# atmegademo.net
KiCad netlist of a schematic drawn in EAGLE
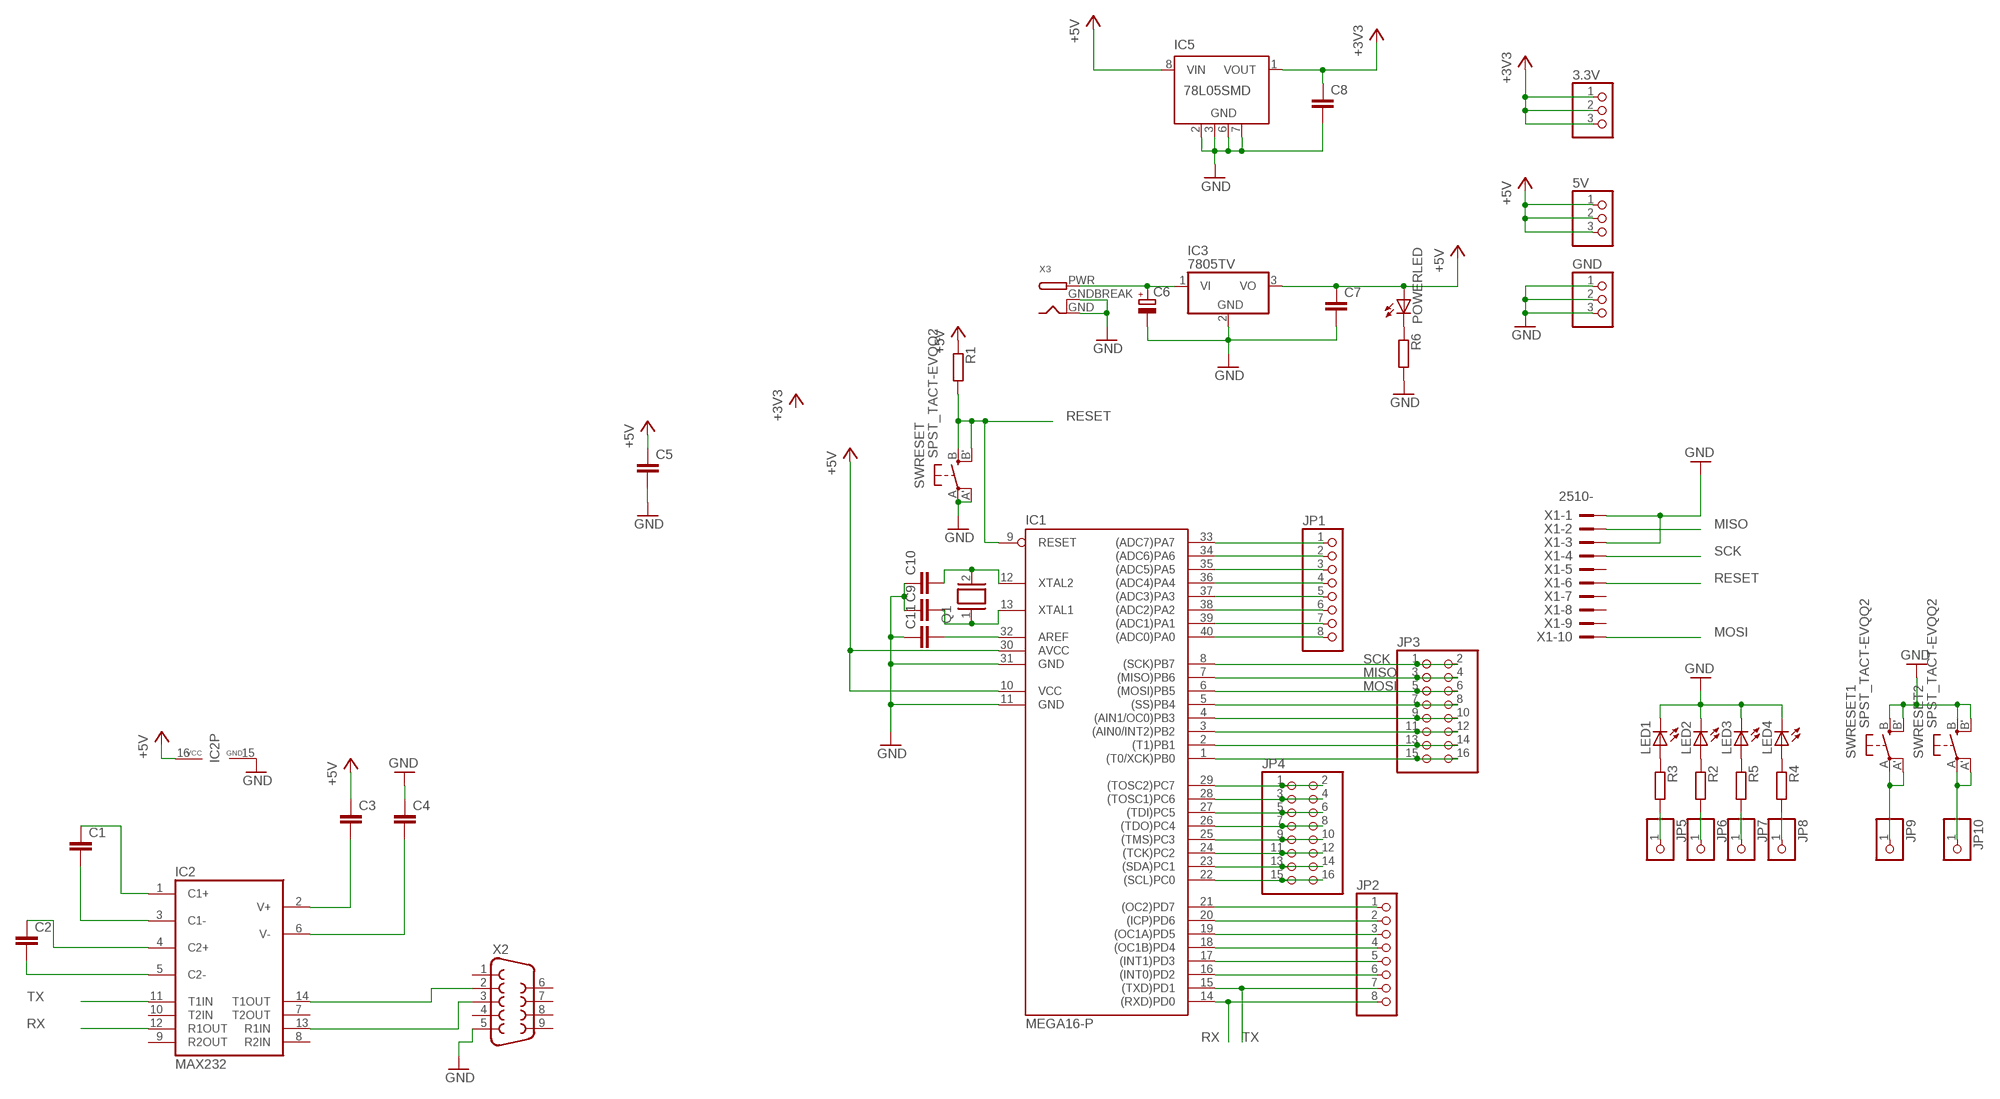
[diagram p0: schematic, sheet 1]

(export (version "E")
  (design (tool "Eeschema 10.0.6"))
  (components
    (comp (ref "3.3V")
      (value "PINHD-1X3")
      (footprint "eagle-import:1X03")
      (libsource (lib "eagle-import") (part "PINHD-1X3"))
    )
    (comp (ref "5V")
      (value "PINHD-1X3")
      (footprint "eagle-import:1X03")
      (libsource (lib "eagle-import") (part "PINHD-1X3"))
    )
    (comp (ref "C1")
      (value "C-EUC0805K")
      (footprint "eagle-import:C0805K")
      (libsource (lib "eagle-import") (part "C-EUC0805K"))
    )
    (comp (ref "C2")
      (value "C-EUC0805K")
      (footprint "eagle-import:C0805K")
      (libsource (lib "eagle-import") (part "C-EUC0805K"))
    )
    (comp (ref "C3")
      (value "C-EUC0805K")
      (footprint "eagle-import:C0805K")
      (libsource (lib "eagle-import") (part "C-EUC0805K"))
    )
    (comp (ref "C4")
      (value "C-EUC0805K")
      (footprint "eagle-import:C0805K")
      (libsource (lib "eagle-import") (part "C-EUC0805K"))
    )
    (comp (ref "C5")
      (value "C-EUC0805K")
      (footprint "eagle-import:C0805K")
      (libsource (lib "eagle-import") (part "C-EUC0805K"))
    )
    (comp (ref "C6")
      (value "CPOL-EUE2.5-5")
      (footprint "eagle-import:E2,5-5")
      (libsource (lib "eagle-import") (part "CPOL-EUE2.5-5"))
    )
    (comp (ref "C7")
      (value "C-EUC0805K")
      (footprint "eagle-import:C0805K")
      (libsource (lib "eagle-import") (part "C-EUC0805K"))
    )
    (comp (ref "C8")
      (value "C-EUC0805K")
      (footprint "eagle-import:C0805K")
      (libsource (lib "eagle-import") (part "C-EUC0805K"))
    )
    (comp (ref "C9")
      (value "C-EU050-025X075")
      (footprint "eagle-import:C050-025X075")
      (libsource (lib "eagle-import") (part "C-EU050-025X075"))
    )
    (comp (ref "C10")
      (value "C-EU050-025X075")
      (footprint "eagle-import:C050-025X075")
      (libsource (lib "eagle-import") (part "C-EU050-025X075"))
    )
    (comp (ref "C11")
      (value "C-EUC0805K")
      (footprint "eagle-import:C0805K")
      (libsource (lib "eagle-import") (part "C-EUC0805K"))
    )
    (comp (ref "GND")
      (value "PINHD-1X3")
      (footprint "eagle-import:1X03")
      (libsource (lib "eagle-import") (part "PINHD-1X3"))
    )
    (comp (ref "IC1")
      (value "MEGA16-P")
      (footprint "eagle-import:DIL40")
      (fields (field (name "MPN") "ATMEGA16-16PU"))
      (libsource (lib "eagle-import") (part "MEGA16-P"))
    )
    (comp (ref "IC2")
      (value "MAX232")
      (footprint "eagle-import:DIL16")
      (fields (field (name "MF") "MAXIM") (field (name "MPN") "MAX232ACPE+"))
      (libsource (lib "eagle-import") (part "MAX232"))
    )
    (comp (ref "IC3")
      (value "7805TV")
      (footprint "eagle-import:TO220V")
      (libsource (lib "eagle-import") (part "78TV05"))
    )
    (comp (ref "IC5")
      (value "78L05SMD")
      (footprint "eagle-import:SO08")
      (libsource (lib "eagle-import") (part "78LSMD05"))
    )
    (comp (ref "JP1")
      (value "PINHD-1X8BIG")
      (footprint "eagle-import:1X08-BIG")
      (libsource (lib "eagle-import") (part "PINHD-1X8BIG"))
    )
    (comp (ref "JP2")
      (value "PINHD-1X8BIG")
      (footprint "eagle-import:1X08-BIG")
      (libsource (lib "eagle-import") (part "PINHD-1X8BIG"))
    )
    (comp (ref "JP3")
      (value "PINHD-2X8")
      (footprint "eagle-import:2X08")
      (libsource (lib "eagle-import") (part "PINHD-2X8"))
    )
    (comp (ref "JP4")
      (value "PINHD-2X8")
      (footprint "eagle-import:2X08")
      (libsource (lib "eagle-import") (part "PINHD-2X8"))
    )
    (comp (ref "JP5")
      (value "PINHD-1X1")
      (footprint "eagle-import:1X01")
      (libsource (lib "eagle-import") (part "PINHD-1X1"))
    )
    (comp (ref "JP6")
      (value "PINHD-1X1")
      (footprint "eagle-import:1X01")
      (libsource (lib "eagle-import") (part "PINHD-1X1"))
    )
    (comp (ref "JP7")
      (value "PINHD-1X1")
      (footprint "eagle-import:1X01")
      (libsource (lib "eagle-import") (part "PINHD-1X1"))
    )
    (comp (ref "JP8")
      (value "PINHD-1X1")
      (footprint "eagle-import:1X01")
      (libsource (lib "eagle-import") (part "PINHD-1X1"))
    )
    (comp (ref "JP9")
      (value "PINHD-1X1")
      (footprint "eagle-import:1X01")
      (libsource (lib "eagle-import") (part "PINHD-1X1"))
    )
    (comp (ref "JP10")
      (value "PINHD-1X1")
      (footprint "eagle-import:1X01")
      (libsource (lib "eagle-import") (part "PINHD-1X1"))
    )
    (comp (ref "LED1")
      (value "LED3MM")
      (footprint "eagle-import:LED3MM")
      (libsource (lib "eagle-import") (part "LED3MM"))
    )
    (comp (ref "LED2")
      (value "LED3MM")
      (footprint "eagle-import:LED3MM")
      (libsource (lib "eagle-import") (part "LED3MM"))
    )
    (comp (ref "LED3")
      (value "LED3MM")
      (footprint "eagle-import:LED3MM")
      (libsource (lib "eagle-import") (part "LED3MM"))
    )
    (comp (ref "LED4")
      (value "LED3MM")
      (footprint "eagle-import:LED3MM")
      (libsource (lib "eagle-import") (part "LED3MM"))
    )
    (comp (ref "POWERLED")
      (value "LED3MM")
      (footprint "eagle-import:LED3MM")
      (libsource (lib "eagle-import") (part "LED3MM"))
    )
    (comp (ref "Q1")
      (value "XTAL/S")
      (footprint "eagle-import:QS")
      (libsource (lib "eagle-import") (part "XTAL/S"))
    )
    (comp (ref "R1")
      (value "R-EU_0207/12")
      (footprint "eagle-import:0207_12")
      (libsource (lib "eagle-import") (part "R-EU_0207/12"))
    )
    (comp (ref "R2")
      (value "R-EU_R0805")
      (footprint "eagle-import:R0805")
      (libsource (lib "eagle-import") (part "R-EU_R0805"))
    )
    (comp (ref "R3")
      (value "R-EU_M0805")
      (footprint "eagle-import:M0805")
      (libsource (lib "eagle-import") (part "R-EU_M0805"))
    )
    (comp (ref "R4")
      (value "R-EU_R0805")
      (footprint "eagle-import:R0805")
      (libsource (lib "eagle-import") (part "R-EU_R0805"))
    )
    (comp (ref "R5")
      (value "R-EU_M0805")
      (footprint "eagle-import:M0805")
      (libsource (lib "eagle-import") (part "R-EU_M0805"))
    )
    (comp (ref "R6")
      (value "R-EU_M0805")
      (footprint "eagle-import:M0805")
      (libsource (lib "eagle-import") (part "R-EU_M0805"))
    )
    (comp (ref "SWRESET")
      (value "SPST_TACT-EVQQ2")
      (footprint "eagle-import:EVQ-Q2")
      (libsource (lib "eagle-import") (part "SPST_TACT-EVQQ2"))
    )
    (comp (ref "SWRESET1")
      (value "SPST_TACT-EVQQ2")
      (footprint "eagle-import:EVQ-Q2")
      (libsource (lib "eagle-import") (part "SPST_TACT-EVQQ2"))
    )
    (comp (ref "SWRESET2")
      (value "SPST_TACT-EVQQ2")
      (footprint "eagle-import:EVQ-Q2")
      (libsource (lib "eagle-import") (part "SPST_TACT-EVQQ2"))
    )
    (comp (ref "X1")
      (value "2510-")
      (footprint "eagle-import:PAK100_2500-10")
      (fields (field (name "MF") "3M") (field (name "MPN") "2510-6002UB"))
      (libsource (lib "eagle-import") (part "2510-"))
    )
    (comp (ref "X2")
      (value "F09H")
      (footprint "eagle-import:F09H")
      (libsource (lib "eagle-import") (part "F09H"))
    )
    (comp (ref "X3")
      (value "DCBARRELPTH")
      (footprint "eagle-import:DCJACK_2MM_PTH")
      (libsource (lib "eagle-import") (part "DCBARRELPTH"))
    )
  )
  (nets
    (net (code "1") (name "+3V3") (class "Default")
      (node (ref "3.3V") (pin "1") (pinfunction "1_1") (pintype "passive"))
      (node (ref "3.3V") (pin "2") (pinfunction "2_2") (pintype "passive"))
      (node (ref "3.3V") (pin "3") (pinfunction "3_3") (pintype "passive"))
      (node (ref "C8") (pin "1") (pinfunction "1_1") (pintype "passive"))
      (node (ref "IC5") (pin "1") (pinfunction "VOUT_1") (pintype "output"))
    )
    (net (code "2") (name "+5V") (class "Default")
      (node (ref "5V") (pin "1") (pinfunction "1_1") (pintype "passive"))
      (node (ref "5V") (pin "2") (pinfunction "2_2") (pintype "passive"))
      (node (ref "5V") (pin "3") (pinfunction "3_3") (pintype "passive"))
      (node (ref "C3") (pin "1") (pinfunction "1_1") (pintype "passive"))
      (node (ref "C5") (pin "1") (pinfunction "1_1") (pintype "passive"))
      (node (ref "C7") (pin "1") (pinfunction "1_1") (pintype "passive"))
      (node (ref "IC1") (pin "10") (pinfunction "VCC_10") (pintype "power_in"))
      (node (ref "IC1") (pin "30") (pinfunction "AVCC_30") (pintype "power_in"))
      (node (ref "IC2") (pin "16") (pinfunction "VCC_16") (pintype "power_in"))
      (node (ref "IC3") (pin "3") (pinfunction "VO_3") (pintype "passive"))
      (node (ref "IC5") (pin "8") (pinfunction "VIN_8") (pintype "passive"))
      (node (ref "POWERLED") (pin "A") (pinfunction "A_A") (pintype "passive"))
      (node (ref "R1") (pin "1") (pinfunction "1_1") (pintype "passive"))
    )
    (net (code "3") (name "/MISO") (class "Default")
      (node (ref "IC1") (pin "7") (pinfunction "(MISO)PB6_7") (pintype "bidirectional"))
      (node (ref "JP3") (pin "3") (pinfunction "3_3") (pintype "passive"))
      (node (ref "JP3") (pin "4") (pinfunction "4_4") (pintype "passive"))
      (node (ref "X1") (pin "2") (pinfunction "KL_2") (pintype "passive"))
    )
    (net (code "4") (name "/MOSI") (class "Default")
      (node (ref "IC1") (pin "6") (pinfunction "(MOSI)PB5_6") (pintype "bidirectional"))
      (node (ref "JP3") (pin "5") (pinfunction "5_5") (pintype "passive"))
      (node (ref "JP3") (pin "6") (pinfunction "6_6") (pintype "passive"))
      (node (ref "X1") (pin "10") (pinfunction "KL_10") (pintype "passive"))
    )
    (net (code "5") (name "/RESET") (class "Default")
      (node (ref "IC1") (pin "9") (pinfunction "RESET_9") (pintype "input"))
      (node (ref "R1") (pin "2") (pinfunction "2_2") (pintype "passive"))
      (node (ref "SWRESET") (pin "B") (pinfunction "S_B") (pintype "passive"))
      (node (ref "SWRESET") (pin "B'") (pinfunction "S1_B'") (pintype "passive"))
      (node (ref "X1") (pin "6") (pinfunction "KL_6") (pintype "passive"))
    )
    (net (code "6") (name "/RX") (class "Default")
      (node (ref "IC1") (pin "14") (pinfunction "(RXD)PD0_14") (pintype "bidirectional"))
      (node (ref "IC2") (pin "12") (pinfunction "R1OUT_12") (pintype "output"))
      (node (ref "JP2") (pin "8") (pinfunction "8_8") (pintype "passive"))
    )
    (net (code "7") (name "/SCK") (class "Default")
      (node (ref "IC1") (pin "8") (pinfunction "(SCK)PB7_8") (pintype "bidirectional"))
      (node (ref "JP3") (pin "1") (pinfunction "1_1") (pintype "passive"))
      (node (ref "JP3") (pin "2") (pinfunction "2_2") (pintype "passive"))
      (node (ref "X1") (pin "4") (pinfunction "KL_4") (pintype "passive"))
    )
    (net (code "8") (name "/TX") (class "Default")
      (node (ref "IC1") (pin "15") (pinfunction "(TXD)PD1_15") (pintype "bidirectional"))
      (node (ref "IC2") (pin "11") (pinfunction "T1IN_11") (pintype "input"))
      (node (ref "JP2") (pin "7") (pinfunction "7_7") (pintype "passive"))
    )
    (net (code "9") (name "GND") (class "Default")
      (node (ref "C10") (pin "1") (pinfunction "1_1") (pintype "passive"))
      (node (ref "C11") (pin "1") (pinfunction "1_1") (pintype "passive"))
      (node (ref "C4") (pin "1") (pinfunction "1_1") (pintype "passive"))
      (node (ref "C5") (pin "2") (pinfunction "2_2") (pintype "passive"))
      (node (ref "C6") (pin "-") (pinfunction "-_-") (pintype "passive"))
      (node (ref "C7") (pin "2") (pinfunction "2_2") (pintype "passive"))
      (node (ref "C8") (pin "2") (pinfunction "2_2") (pintype "passive"))
      (node (ref "C9") (pin "1") (pinfunction "1_1") (pintype "passive"))
      (node (ref "GND") (pin "1") (pinfunction "1_1") (pintype "passive"))
      (node (ref "GND") (pin "2") (pinfunction "2_2") (pintype "passive"))
      (node (ref "GND") (pin "3") (pinfunction "3_3") (pintype "passive"))
      (node (ref "IC1") (pin "11") (pinfunction "GND_11") (pintype "power_in"))
      (node (ref "IC1") (pin "31") (pinfunction "GND_31") (pintype "power_in"))
      (node (ref "IC2") (pin "15") (pinfunction "GND_15") (pintype "power_in"))
      (node (ref "IC3") (pin "2") (pinfunction "GND_2") (pintype "passive"))
      (node (ref "IC5") (pin "2") (pinfunction "GND_2") (pintype "power_in"))
      (node (ref "IC5") (pin "3") (pinfunction "GND_3") (pintype "power_in"))
      (node (ref "IC5") (pin "6") (pinfunction "GND_6") (pintype "power_in"))
      (node (ref "IC5") (pin "7") (pinfunction "GND_7") (pintype "power_in"))
      (node (ref "LED1") (pin "K") (pinfunction "C_K") (pintype "passive"))
      (node (ref "LED2") (pin "K") (pinfunction "C_K") (pintype "passive"))
      (node (ref "LED3") (pin "K") (pinfunction "C_K") (pintype "passive"))
      (node (ref "LED4") (pin "K") (pinfunction "C_K") (pintype "passive"))
      (node (ref "R6") (pin "2") (pinfunction "2_2") (pintype "passive"))
      (node (ref "SWRESET") (pin "A") (pinfunction "P_A") (pintype "passive"))
      (node (ref "SWRESET") (pin "A'") (pinfunction "P1_A'") (pintype "passive"))
      (node (ref "SWRESET1") (pin "B") (pinfunction "S_B") (pintype "passive"))
      (node (ref "SWRESET1") (pin "B'") (pinfunction "S1_B'") (pintype "passive"))
      (node (ref "SWRESET2") (pin "B") (pinfunction "S_B") (pintype "passive"))
      (node (ref "SWRESET2") (pin "B'") (pinfunction "S1_B'") (pintype "passive"))
      (node (ref "X1") (pin "1") (pinfunction "KL_1") (pintype "passive"))
      (node (ref "X1") (pin "3") (pinfunction "KL_3") (pintype "passive"))
      (node (ref "X2") (pin "5") (pinfunction "5_5") (pintype "passive"))
      (node (ref "X3") (pin "GND") (pinfunction "GND_GND") (pintype "power_in"))
      (node (ref "X3") (pin "GNDBREAK") (pinfunction "GNDBREAK_GNDBREAK") (pintype "power_in"))
    )
    (net (code "10") (name "Net-(IC1-(ADC0)PA0)") (class "Default")
      (node (ref "IC1") (pin "40") (pinfunction "(ADC0)PA0_40") (pintype "bidirectional"))
      (node (ref "JP1") (pin "8") (pinfunction "8_8") (pintype "passive"))
    )
    (net (code "11") (name "Net-(IC1-(ADC1)PA1)") (class "Default")
      (node (ref "IC1") (pin "39") (pinfunction "(ADC1)PA1_39") (pintype "bidirectional"))
      (node (ref "JP1") (pin "7") (pinfunction "7_7") (pintype "passive"))
    )
    (net (code "12") (name "Net-(IC1-(ADC2)PA2)") (class "Default")
      (node (ref "IC1") (pin "38") (pinfunction "(ADC2)PA2_38") (pintype "bidirectional"))
      (node (ref "JP1") (pin "6") (pinfunction "6_6") (pintype "passive"))
    )
    (net (code "13") (name "Net-(IC1-(ADC3)PA3)") (class "Default")
      (node (ref "IC1") (pin "37") (pinfunction "(ADC3)PA3_37") (pintype "bidirectional"))
      (node (ref "JP1") (pin "5") (pinfunction "5_5") (pintype "passive"))
    )
    (net (code "14") (name "Net-(IC1-(ADC4)PA4)") (class "Default")
      (node (ref "IC1") (pin "36") (pinfunction "(ADC4)PA4_36") (pintype "bidirectional"))
      (node (ref "JP1") (pin "4") (pinfunction "4_4") (pintype "passive"))
    )
    (net (code "15") (name "Net-(IC1-(ADC5)PA5)") (class "Default")
      (node (ref "IC1") (pin "35") (pinfunction "(ADC5)PA5_35") (pintype "bidirectional"))
      (node (ref "JP1") (pin "3") (pinfunction "3_3") (pintype "passive"))
    )
    (net (code "16") (name "Net-(IC1-(ADC6)PA6)") (class "Default")
      (node (ref "IC1") (pin "34") (pinfunction "(ADC6)PA6_34") (pintype "bidirectional"))
      (node (ref "JP1") (pin "2") (pinfunction "2_2") (pintype "passive"))
    )
    (net (code "17") (name "Net-(IC1-(ADC7)PA7)") (class "Default")
      (node (ref "IC1") (pin "33") (pinfunction "(ADC7)PA7_33") (pintype "bidirectional"))
      (node (ref "JP1") (pin "1") (pinfunction "1_1") (pintype "passive"))
    )
    (net (code "18") (name "Net-(IC1-(AIN0{slash}INT2)PB2)") (class "Default")
      (node (ref "IC1") (pin "3") (pinfunction "(AIN0/INT2)PB2_3") (pintype "bidirectional"))
      (node (ref "JP3") (pin "11") (pinfunction "11_11") (pintype "passive"))
      (node (ref "JP3") (pin "12") (pinfunction "12_12") (pintype "passive"))
    )
    (net (code "19") (name "Net-(IC1-(AIN1{slash}OC0)PB3)") (class "Default")
      (node (ref "IC1") (pin "4") (pinfunction "(AIN1/OC0)PB3_4") (pintype "bidirectional"))
      (node (ref "JP3") (pin "10") (pinfunction "10_10") (pintype "passive"))
      (node (ref "JP3") (pin "9") (pinfunction "9_9") (pintype "passive"))
    )
    (net (code "20") (name "Net-(IC1-(ICP)PD6)") (class "Default")
      (node (ref "IC1") (pin "20") (pinfunction "(ICP)PD6_20") (pintype "bidirectional"))
      (node (ref "JP2") (pin "2") (pinfunction "2_2") (pintype "passive"))
    )
    (net (code "21") (name "Net-(IC1-(INT0)PD2)") (class "Default")
      (node (ref "IC1") (pin "16") (pinfunction "(INT0)PD2_16") (pintype "bidirectional"))
      (node (ref "JP2") (pin "6") (pinfunction "6_6") (pintype "passive"))
    )
    (net (code "22") (name "Net-(IC1-(INT1)PD3)") (class "Default")
      (node (ref "IC1") (pin "17") (pinfunction "(INT1)PD3_17") (pintype "bidirectional"))
      (node (ref "JP2") (pin "5") (pinfunction "5_5") (pintype "passive"))
    )
    (net (code "23") (name "Net-(IC1-(OC1A)PD5)") (class "Default")
      (node (ref "IC1") (pin "19") (pinfunction "(OC1A)PD5_19") (pintype "bidirectional"))
      (node (ref "JP2") (pin "3") (pinfunction "3_3") (pintype "passive"))
    )
    (net (code "24") (name "Net-(IC1-(OC1B)PD4)") (class "Default")
      (node (ref "IC1") (pin "18") (pinfunction "(OC1B)PD4_18") (pintype "bidirectional"))
      (node (ref "JP2") (pin "4") (pinfunction "4_4") (pintype "passive"))
    )
    (net (code "25") (name "Net-(IC1-(OC2)PD7)") (class "Default")
      (node (ref "IC1") (pin "21") (pinfunction "(OC2)PD7_21") (pintype "bidirectional"))
      (node (ref "JP2") (pin "1") (pinfunction "1_1") (pintype "passive"))
    )
    (net (code "26") (name "Net-(IC1-(SCL)PC0)") (class "Default")
      (node (ref "IC1") (pin "22") (pinfunction "(SCL)PC0_22") (pintype "bidirectional"))
      (node (ref "JP4") (pin "15") (pinfunction "15_15") (pintype "passive"))
      (node (ref "JP4") (pin "16") (pinfunction "16_16") (pintype "passive"))
    )
    (net (code "27") (name "Net-(IC1-(SDA)PC1)") (class "Default")
      (node (ref "IC1") (pin "23") (pinfunction "(SDA)PC1_23") (pintype "bidirectional"))
      (node (ref "JP4") (pin "13") (pinfunction "13_13") (pintype "passive"))
      (node (ref "JP4") (pin "14") (pinfunction "14_14") (pintype "passive"))
    )
    (net (code "28") (name "Net-(IC1-(SS)PB4)") (class "Default")
      (node (ref "IC1") (pin "5") (pinfunction "(SS)PB4_5") (pintype "bidirectional"))
      (node (ref "JP3") (pin "7") (pinfunction "7_7") (pintype "passive"))
      (node (ref "JP3") (pin "8") (pinfunction "8_8") (pintype "passive"))
    )
    (net (code "29") (name "Net-(IC1-(T0{slash}XCK)PB0)") (class "Default")
      (node (ref "IC1") (pin "1") (pinfunction "(T0/XCK)PB0_1") (pintype "bidirectional"))
      (node (ref "JP3") (pin "15") (pinfunction "15_15") (pintype "passive"))
      (node (ref "JP3") (pin "16") (pinfunction "16_16") (pintype "passive"))
    )
    (net (code "30") (name "Net-(IC1-(T1)PB1)") (class "Default")
      (node (ref "IC1") (pin "2") (pinfunction "(T1)PB1_2") (pintype "bidirectional"))
      (node (ref "JP3") (pin "13") (pinfunction "13_13") (pintype "passive"))
      (node (ref "JP3") (pin "14") (pinfunction "14_14") (pintype "passive"))
    )
    (net (code "31") (name "Net-(IC1-(TCK)PC2)") (class "Default")
      (node (ref "IC1") (pin "24") (pinfunction "(TCK)PC2_24") (pintype "bidirectional"))
      (node (ref "JP4") (pin "11") (pinfunction "11_11") (pintype "passive"))
      (node (ref "JP4") (pin "12") (pinfunction "12_12") (pintype "passive"))
    )
    (net (code "32") (name "Net-(IC1-(TDI)PC5)") (class "Default")
      (node (ref "IC1") (pin "27") (pinfunction "(TDI)PC5_27") (pintype "bidirectional"))
      (node (ref "JP4") (pin "5") (pinfunction "5_5") (pintype "passive"))
      (node (ref "JP4") (pin "6") (pinfunction "6_6") (pintype "passive"))
    )
    (net (code "33") (name "Net-(IC1-(TDO)PC4)") (class "Default")
      (node (ref "IC1") (pin "26") (pinfunction "(TDO)PC4_26") (pintype "bidirectional"))
      (node (ref "JP4") (pin "7") (pinfunction "7_7") (pintype "passive"))
      (node (ref "JP4") (pin "8") (pinfunction "8_8") (pintype "passive"))
    )
    (net (code "34") (name "Net-(IC1-(TMS)PC3)") (class "Default")
      (node (ref "IC1") (pin "25") (pinfunction "(TMS)PC3_25") (pintype "bidirectional"))
      (node (ref "JP4") (pin "10") (pinfunction "10_10") (pintype "passive"))
      (node (ref "JP4") (pin "9") (pinfunction "9_9") (pintype "passive"))
    )
    (net (code "35") (name "Net-(IC1-(TOSC1)PC6)") (class "Default")
      (node (ref "IC1") (pin "28") (pinfunction "(TOSC1)PC6_28") (pintype "bidirectional"))
      (node (ref "JP4") (pin "3") (pinfunction "3_3") (pintype "passive"))
      (node (ref "JP4") (pin "4") (pinfunction "4_4") (pintype "passive"))
    )
    (net (code "36") (name "Net-(IC1-(TOSC2)PC7)") (class "Default")
      (node (ref "IC1") (pin "29") (pinfunction "(TOSC2)PC7_29") (pintype "bidirectional"))
      (node (ref "JP4") (pin "1") (pinfunction "1_1") (pintype "passive"))
      (node (ref "JP4") (pin "2") (pinfunction "2_2") (pintype "passive"))
    )
    (net (code "37") (name "Net-(IC1-AREF)") (class "Default")
      (node (ref "C11") (pin "2") (pinfunction "2_2") (pintype "passive"))
      (node (ref "IC1") (pin "32") (pinfunction "AREF_32") (pintype "passive"))
    )
    (net (code "38") (name "Net-(IC1-XTAL1)") (class "Default")
      (node (ref "C9") (pin "2") (pinfunction "2_2") (pintype "passive"))
      (node (ref "IC1") (pin "13") (pinfunction "XTAL1_13") (pintype "bidirectional"))
      (node (ref "Q1") (pin "1") (pinfunction "1_1") (pintype "passive"))
    )
    (net (code "39") (name "Net-(IC1-XTAL2)") (class "Default")
      (node (ref "C10") (pin "2") (pinfunction "2_2") (pintype "passive"))
      (node (ref "IC1") (pin "12") (pinfunction "XTAL2_12") (pintype "bidirectional"))
      (node (ref "Q1") (pin "2") (pinfunction "2_2") (pintype "passive"))
    )
    (net (code "40") (name "Net-(IC2A-C1+)") (class "Default")
      (node (ref "C1") (pin "1") (pinfunction "1_1") (pintype "passive"))
      (node (ref "IC2") (pin "1") (pinfunction "C1+_1") (pintype "bidirectional"))
    )
    (net (code "41") (name "Net-(IC2A-C1-)") (class "Default")
      (node (ref "C1") (pin "2") (pinfunction "2_2") (pintype "passive"))
      (node (ref "IC2") (pin "3") (pinfunction "C1-_3") (pintype "bidirectional"))
    )
    (net (code "42") (name "Net-(IC2A-C2+)") (class "Default")
      (node (ref "C2") (pin "1") (pinfunction "1_1") (pintype "passive"))
      (node (ref "IC2") (pin "4") (pinfunction "C2+_4") (pintype "bidirectional"))
    )
    (net (code "43") (name "Net-(IC2A-C2-)") (class "Default")
      (node (ref "C2") (pin "2") (pinfunction "2_2") (pintype "passive"))
      (node (ref "IC2") (pin "5") (pinfunction "C2-_5") (pintype "bidirectional"))
    )
    (net (code "44") (name "Net-(IC2A-R1IN)") (class "Default")
      (node (ref "IC2") (pin "13") (pinfunction "R1IN_13") (pintype "input"))
      (node (ref "X2") (pin "3") (pinfunction "3_3") (pintype "passive"))
    )
    (net (code "45") (name "Net-(IC2A-T1OUT)") (class "Default")
      (node (ref "IC2") (pin "14") (pinfunction "T1OUT_14") (pintype "output"))
      (node (ref "X2") (pin "2") (pinfunction "2_2") (pintype "passive"))
    )
    (net (code "46") (name "Net-(IC2A-V+)") (class "Default")
      (node (ref "C3") (pin "2") (pinfunction "2_2") (pintype "passive"))
      (node (ref "IC2") (pin "2") (pinfunction "V+_2") (pintype "bidirectional"))
    )
    (net (code "47") (name "Net-(IC2A-V-)") (class "Default")
      (node (ref "C4") (pin "2") (pinfunction "2_2") (pintype "passive"))
      (node (ref "IC2") (pin "6") (pinfunction "V-_6") (pintype "bidirectional"))
    )
    (net (code "48") (name "Net-(IC3-VI)") (class "Default")
      (node (ref "C6") (pin "+") (pinfunction "+_+") (pintype "passive"))
      (node (ref "IC3") (pin "1") (pinfunction "VI_1") (pintype "input"))
      (node (ref "X3") (pin "PWR") (pinfunction "PWR_PWR") (pintype "power_in"))
    )
    (net (code "49") (name "Net-(JP5-Pad1)") (class "Default")
      (node (ref "JP5") (pin "1") (pinfunction "1_1") (pintype "passive"))
      (node (ref "R3") (pin "2") (pinfunction "2_2") (pintype "passive"))
    )
    (net (code "50") (name "Net-(JP6-Pad1)") (class "Default")
      (node (ref "JP6") (pin "1") (pinfunction "1_1") (pintype "passive"))
      (node (ref "R2") (pin "2") (pinfunction "2_2") (pintype "passive"))
    )
    (net (code "51") (name "Net-(JP7-Pad1)") (class "Default")
      (node (ref "JP7") (pin "1") (pinfunction "1_1") (pintype "passive"))
      (node (ref "R5") (pin "2") (pinfunction "2_2") (pintype "passive"))
    )
    (net (code "52") (name "Net-(JP8-Pad1)") (class "Default")
      (node (ref "JP8") (pin "1") (pinfunction "1_1") (pintype "passive"))
      (node (ref "R4") (pin "2") (pinfunction "2_2") (pintype "passive"))
    )
    (net (code "53") (name "Net-(LED1-PadA)") (class "Default")
      (node (ref "LED1") (pin "A") (pinfunction "A_A") (pintype "passive"))
      (node (ref "R3") (pin "1") (pinfunction "1_1") (pintype "passive"))
    )
    (net (code "54") (name "Net-(LED2-PadA)") (class "Default")
      (node (ref "LED2") (pin "A") (pinfunction "A_A") (pintype "passive"))
      (node (ref "R2") (pin "1") (pinfunction "1_1") (pintype "passive"))
    )
    (net (code "55") (name "Net-(LED3-PadA)") (class "Default")
      (node (ref "LED3") (pin "A") (pinfunction "A_A") (pintype "passive"))
      (node (ref "R5") (pin "1") (pinfunction "1_1") (pintype "passive"))
    )
    (net (code "56") (name "Net-(LED4-PadA)") (class "Default")
      (node (ref "LED4") (pin "A") (pinfunction "A_A") (pintype "passive"))
      (node (ref "R4") (pin "1") (pinfunction "1_1") (pintype "passive"))
    )
    (net (code "57") (name "Net-(POWERLED-C)") (class "Default")
      (node (ref "POWERLED") (pin "K") (pinfunction "C_K") (pintype "passive"))
      (node (ref "R6") (pin "1") (pinfunction "1_1") (pintype "passive"))
    )
    (net (code "58") (name "Net-(SWRESET1-P)") (class "Default")
      (node (ref "JP9") (pin "1") (pinfunction "1_1") (pintype "passive"))
      (node (ref "SWRESET1") (pin "A") (pinfunction "P_A") (pintype "passive"))
      (node (ref "SWRESET1") (pin "A'") (pinfunction "P1_A'") (pintype "passive"))
    )
    (net (code "59") (name "Net-(SWRESET2-P)") (class "Default")
      (node (ref "JP10") (pin "1") (pinfunction "1_1") (pintype "passive"))
      (node (ref "SWRESET2") (pin "A") (pinfunction "P_A") (pintype "passive"))
      (node (ref "SWRESET2") (pin "A'") (pinfunction "P1_A'") (pintype "passive"))
    )
    (net (code "60") (name "unconnected-(IC2A-R2IN-Pad8)") (class "Default")
      (node (ref "IC2") (pin "8") (pinfunction "R2IN_8") (pintype "input"))
    )
    (net (code "61") (name "unconnected-(IC2A-R2OUT-Pad9)") (class "Default")
      (node (ref "IC2") (pin "9") (pinfunction "R2OUT_9") (pintype "output"))
    )
    (net (code "62") (name "unconnected-(IC2A-T2IN-Pad10)") (class "Default")
      (node (ref "IC2") (pin "10") (pinfunction "T2IN_10") (pintype "input"))
    )
    (net (code "63") (name "unconnected-(IC2A-T2OUT-Pad7)") (class "Default")
      (node (ref "IC2") (pin "7") (pinfunction "T2OUT_7") (pintype "output"))
    )
    (net (code "64") (name "unconnected-(X1F-KL-Pad5)") (class "Default")
      (node (ref "X1") (pin "5") (pinfunction "KL_5") (pintype "passive"))
    )
    (net (code "65") (name "unconnected-(X1H-KL-Pad7)") (class "Default")
      (node (ref "X1") (pin "7") (pinfunction "KL_7") (pintype "passive"))
    )
    (net (code "66") (name "unconnected-(X1I-KL-Pad8)") (class "Default")
      (node (ref "X1") (pin "8") (pinfunction "KL_8") (pintype "passive"))
    )
    (net (code "67") (name "unconnected-(X1J-KL-Pad9)") (class "Default")
      (node (ref "X1") (pin "9") (pinfunction "KL_9") (pintype "passive"))
    )
    (net (code "68") (name "unconnected-(X2-Pad1)") (class "Default")
      (node (ref "X2") (pin "1") (pinfunction "1_1") (pintype "passive"))
    )
    (net (code "69") (name "unconnected-(X2-Pad4)") (class "Default")
      (node (ref "X2") (pin "4") (pinfunction "4_4") (pintype "passive"))
    )
    (net (code "70") (name "unconnected-(X2-Pad6)") (class "Default")
      (node (ref "X2") (pin "6") (pinfunction "6_6") (pintype "passive"))
    )
    (net (code "71") (name "unconnected-(X2-Pad7)") (class "Default")
      (node (ref "X2") (pin "7") (pinfunction "7_7") (pintype "passive"))
    )
    (net (code "72") (name "unconnected-(X2-Pad8)") (class "Default")
      (node (ref "X2") (pin "8") (pinfunction "8_8") (pintype "passive"))
    )
    (net (code "73") (name "unconnected-(X2-Pad9)") (class "Default")
      (node (ref "X2") (pin "9") (pinfunction "9_9") (pintype "passive"))
    )
  )
)
